# 11-Switch_Strapping.net
KiCad netlist of a schematic drawn in Altium Designer
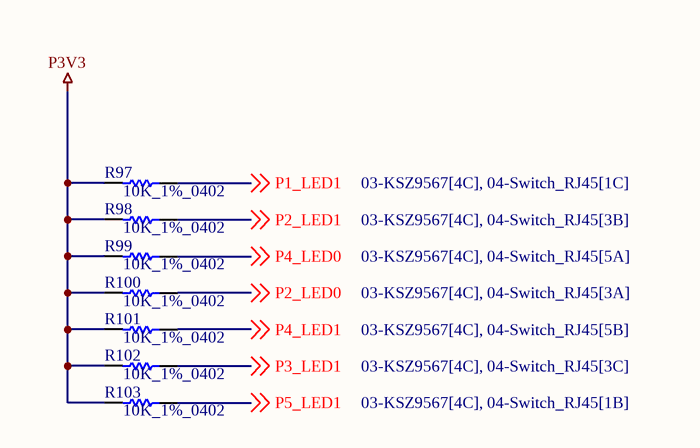
[diagram p0: 11-Switch_Strapping.SchDoc]

(export (version "E")
  (design (tool "Eeschema 10.0.6"))
  (components
    (comp (ref "R97")
      (value "10K_1%_0402")
      (footprint "RESC1005X40X25NL10T10")
      (fields (field (name "MANUFACTURER") "Bourns") (field (name "PART NUMBER") "CR0402-FX-1002GLF"))
      (libsource (lib "Altium Content Vault") (part "RES"))
    )
    (comp (ref "R98")
      (value "10K_1%_0402")
      (footprint "RESC1005X40X25NL10T10")
      (fields (field (name "MANUFACTURER") "Bourns") (field (name "PART NUMBER") "CR0402-FX-1002GLF"))
      (libsource (lib "Altium Content Vault") (part "RES"))
    )
    (comp (ref "R99")
      (value "10K_1%_0402")
      (footprint "RESC1005X40X25NL10T10")
      (fields (field (name "MANUFACTURER") "Bourns") (field (name "PART NUMBER") "CR0402-FX-1002GLF"))
      (libsource (lib "Altium Content Vault") (part "RES"))
    )
    (comp (ref "R100")
      (value "10K_1%_0402")
      (footprint "RESC1005X40X25NL10T10")
      (fields (field (name "MANUFACTURER") "Bourns") (field (name "PART NUMBER") "CR0402-FX-1002GLF"))
      (libsource (lib "Altium Content Vault") (part "RES"))
    )
    (comp (ref "R101")
      (value "10K_1%_0402")
      (footprint "RESC1005X40X25NL10T10")
      (fields (field (name "MANUFACTURER") "Bourns") (field (name "PART NUMBER") "CR0402-FX-1002GLF"))
      (libsource (lib "Altium Content Vault") (part "RES"))
    )
    (comp (ref "R102")
      (value "10K_1%_0402")
      (footprint "RESC1005X40X25NL10T10")
      (fields (field (name "MANUFACTURER") "Bourns") (field (name "PART NUMBER") "CR0402-FX-1002GLF"))
      (libsource (lib "Altium Content Vault") (part "RES"))
    )
    (comp (ref "R103")
      (value "10K_1%_0402")
      (footprint "RESC1005X40X25NL10T10")
      (fields (field (name "MANUFACTURER") "Bourns") (field (name "PART NUMBER") "CR0402-FX-1002GLF"))
      (libsource (lib "Altium Content Vault") (part "RES"))
    )
  )
  (nets
    (net (code "1") (name "P1_LED1") (class "Default")
      (node (ref "R97") (pin "1") (pinfunction "1_1") (pintype "passive"))
    )
    (net (code "2") (name "P2_LED0") (class "Default")
      (node (ref "R100") (pin "1") (pinfunction "1_1") (pintype "passive"))
    )
    (net (code "3") (name "P2_LED1") (class "Default")
      (node (ref "R98") (pin "1") (pinfunction "1_1") (pintype "passive"))
    )
    (net (code "4") (name "P3V3") (class "Default")
      (node (ref "R100") (pin "2") (pinfunction "2_2") (pintype "passive"))
      (node (ref "R101") (pin "2") (pinfunction "2_2") (pintype "passive"))
      (node (ref "R102") (pin "2") (pinfunction "2_2") (pintype "passive"))
      (node (ref "R103") (pin "2") (pinfunction "2_2") (pintype "passive"))
      (node (ref "R97") (pin "2") (pinfunction "2_2") (pintype "passive"))
      (node (ref "R98") (pin "2") (pinfunction "2_2") (pintype "passive"))
      (node (ref "R99") (pin "2") (pinfunction "2_2") (pintype "passive"))
    )
    (net (code "5") (name "P3_LED1") (class "Default")
      (node (ref "R102") (pin "1") (pinfunction "1_1") (pintype "passive"))
    )
    (net (code "6") (name "P4_LED0") (class "Default")
      (node (ref "R99") (pin "1") (pinfunction "1_1") (pintype "passive"))
    )
    (net (code "7") (name "P4_LED1") (class "Default")
      (node (ref "R101") (pin "1") (pinfunction "1_1") (pintype "passive"))
    )
    (net (code "8") (name "P5_LED1") (class "Default")
      (node (ref "R103") (pin "1") (pinfunction "1_1") (pintype "passive"))
    )
  )
)
